# autoset-sensing.net
KiCad netlist of a schematic drawn in EAGLE
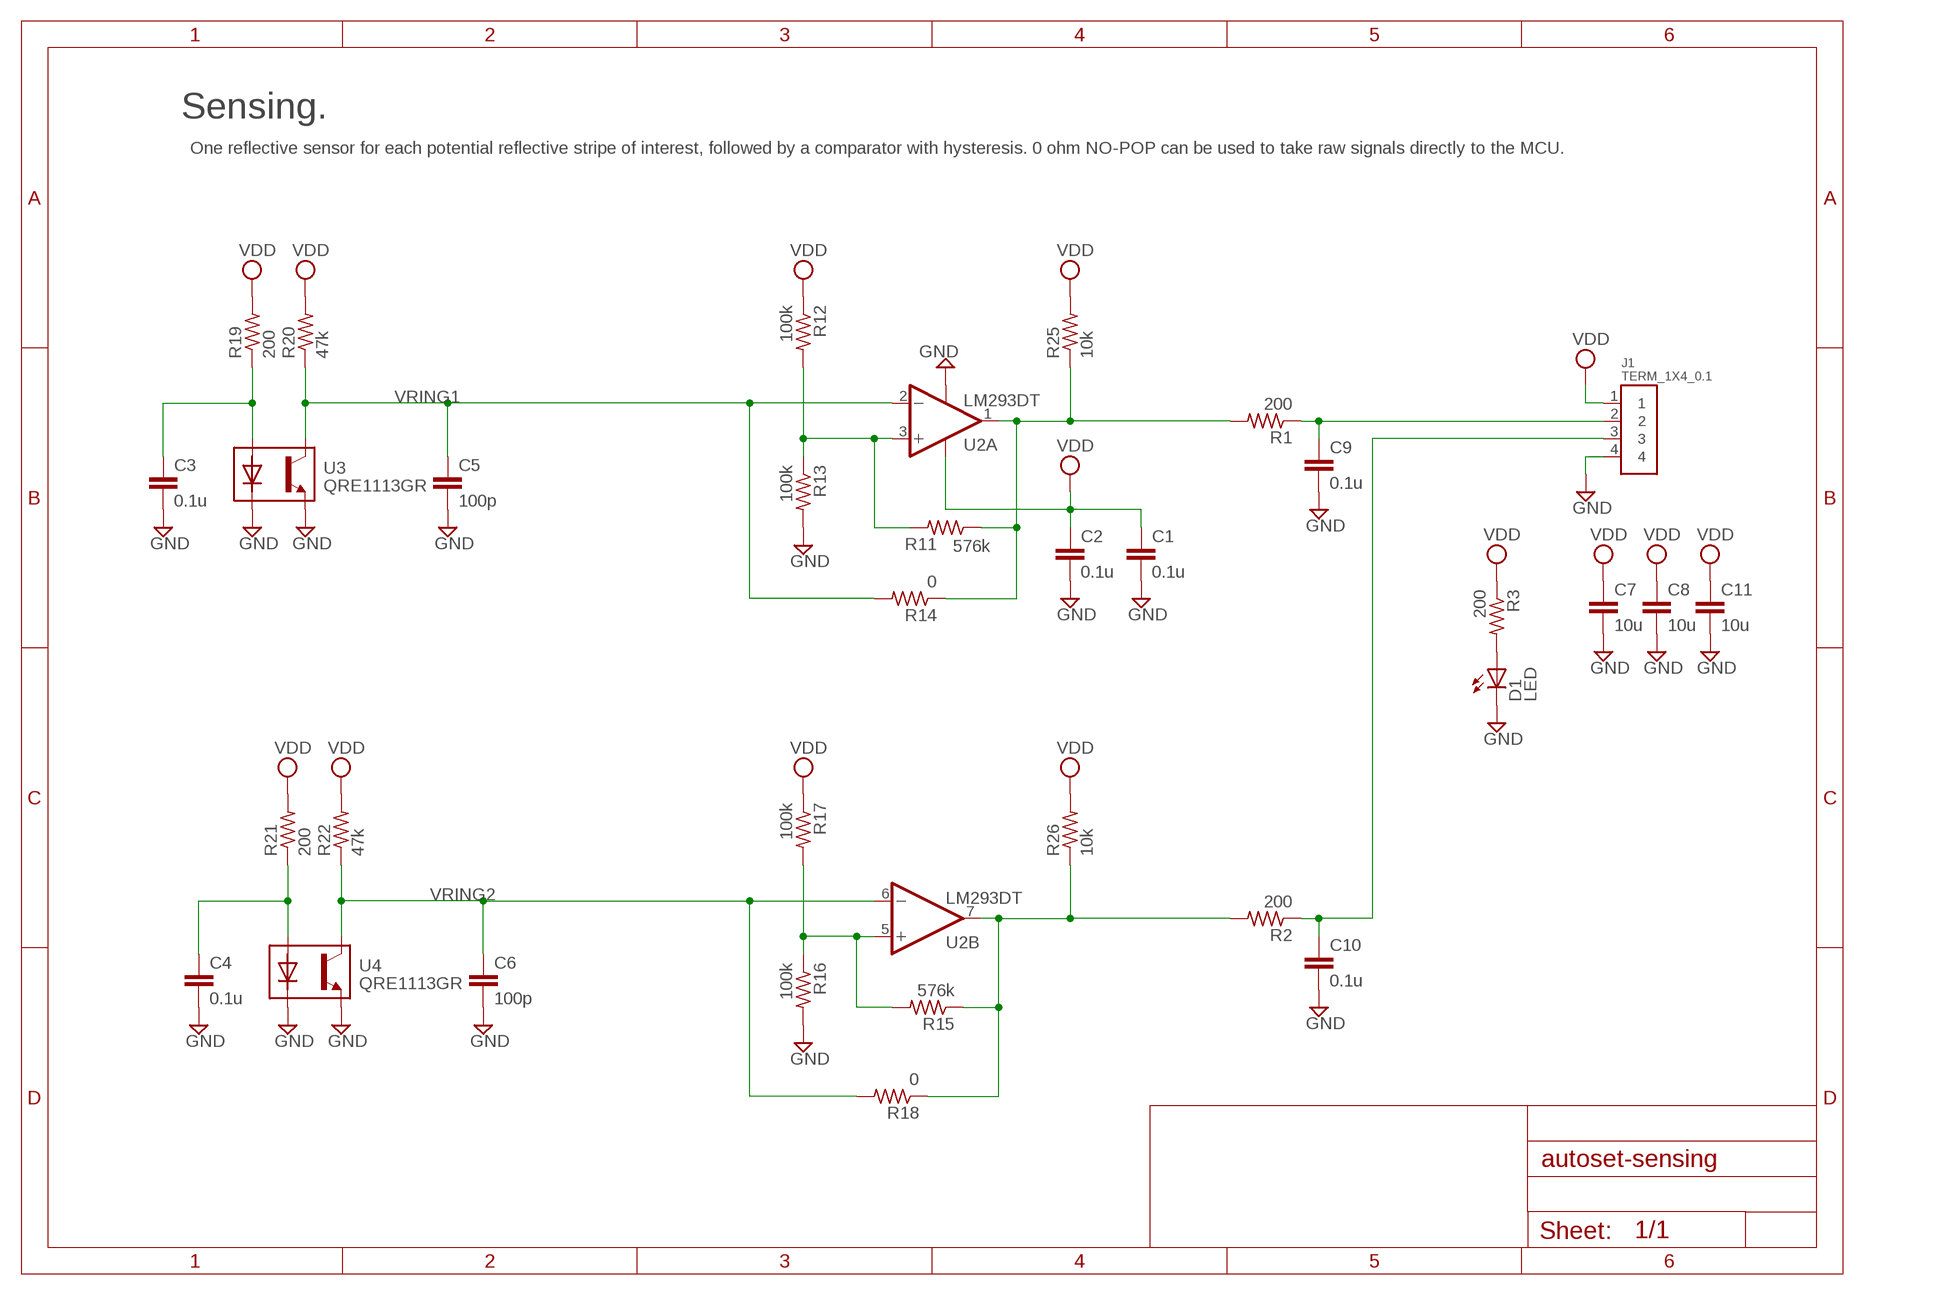
[diagram p0: schematic, sheet 1]

(export (version "E")
  (design (tool "Eeschema 10.0.6"))
  (components
    (comp (ref "C1")
      (value "0.1u")
      (footprint "eagle-import:C0603")
      (libsource (lib "eagle-import") (part "C0603"))
    )
    (comp (ref "C2")
      (value "0.1u")
      (footprint "eagle-import:C0603")
      (libsource (lib "eagle-import") (part "C0603"))
    )
    (comp (ref "C3")
      (value "0.1u")
      (footprint "eagle-import:C0603")
      (libsource (lib "eagle-import") (part "C0603"))
    )
    (comp (ref "C4")
      (value "0.1u")
      (footprint "eagle-import:C0603")
      (libsource (lib "eagle-import") (part "C0603"))
    )
    (comp (ref "C5")
      (value "100p")
      (footprint "eagle-import:C0603")
      (libsource (lib "eagle-import") (part "C0603"))
    )
    (comp (ref "C6")
      (value "100p")
      (footprint "eagle-import:C0603")
      (libsource (lib "eagle-import") (part "C0603"))
    )
    (comp (ref "C7")
      (value "10u")
      (footprint "eagle-import:C0603")
      (libsource (lib "eagle-import") (part "C0603"))
    )
    (comp (ref "C8")
      (value "10u")
      (footprint "eagle-import:C0603")
      (libsource (lib "eagle-import") (part "C0603"))
    )
    (comp (ref "C9")
      (value "0.1u")
      (footprint "eagle-import:C0603")
      (libsource (lib "eagle-import") (part "C0603"))
    )
    (comp (ref "C10")
      (value "0.1u")
      (footprint "eagle-import:C0603")
      (libsource (lib "eagle-import") (part "C0603"))
    )
    (comp (ref "C11")
      (value "10u")
      (footprint "eagle-import:C0603")
      (libsource (lib "eagle-import") (part "C0603"))
    )
    (comp (ref "D1")
      (value "LED")
      (footprint "eagle-import:L0805")
      (libsource (lib "eagle-import") (part "LED"))
    )
    (comp (ref "J1")
      (value "TERM_1X4_0.1")
      (footprint "eagle-import:TERM_1X4_0.1")
      (libsource (lib "eagle-import") (part "TERM_1X4_0.1"))
    )
    (comp (ref "R1")
      (value "200")
      (footprint "eagle-import:R0603")
      (libsource (lib "eagle-import") (part "R0603"))
    )
    (comp (ref "R2")
      (value "200")
      (footprint "eagle-import:R0603")
      (libsource (lib "eagle-import") (part "R0603"))
    )
    (comp (ref "R3")
      (value "200")
      (footprint "eagle-import:R0603")
      (libsource (lib "eagle-import") (part "R0603"))
    )
    (comp (ref "R11")
      (value "576k")
      (footprint "eagle-import:R0603")
      (libsource (lib "eagle-import") (part "R0603"))
    )
    (comp (ref "R12")
      (value "100k")
      (footprint "eagle-import:R0603")
      (libsource (lib "eagle-import") (part "R0603"))
    )
    (comp (ref "R13")
      (value "100k")
      (footprint "eagle-import:R0603")
      (libsource (lib "eagle-import") (part "R0603"))
    )
    (comp (ref "R14")
      (value "0")
      (footprint "eagle-import:R0603")
      (libsource (lib "eagle-import") (part "R0603"))
    )
    (comp (ref "R15")
      (value "576k")
      (footprint "eagle-import:R0603")
      (libsource (lib "eagle-import") (part "R0603"))
    )
    (comp (ref "R16")
      (value "100k")
      (footprint "eagle-import:R0603")
      (libsource (lib "eagle-import") (part "R0603"))
    )
    (comp (ref "R17")
      (value "100k")
      (footprint "eagle-import:R0603")
      (libsource (lib "eagle-import") (part "R0603"))
    )
    (comp (ref "R18")
      (value "0")
      (footprint "eagle-import:R0603")
      (libsource (lib "eagle-import") (part "R0603"))
    )
    (comp (ref "R19")
      (value "200")
      (footprint "eagle-import:R0603")
      (libsource (lib "eagle-import") (part "R0603"))
    )
    (comp (ref "R20")
      (value "47k")
      (footprint "eagle-import:R0603")
      (libsource (lib "eagle-import") (part "R0603"))
    )
    (comp (ref "R21")
      (value "200")
      (footprint "eagle-import:R0603")
      (libsource (lib "eagle-import") (part "R0603"))
    )
    (comp (ref "R22")
      (value "47k")
      (footprint "eagle-import:R0603")
      (libsource (lib "eagle-import") (part "R0603"))
    )
    (comp (ref "R25")
      (value "10k")
      (footprint "eagle-import:R0603")
      (libsource (lib "eagle-import") (part "R0603"))
    )
    (comp (ref "R26")
      (value "10k")
      (footprint "eagle-import:R0603")
      (libsource (lib "eagle-import") (part "R0603"))
    )
    (comp (ref "U2")
      (value "LM293DT")
      (footprint "eagle-import:SOIC8")
      (fields (field (name "DKPN") "497-1566-1-ND"))
      (libsource (lib "eagle-import") (part "LM293DT"))
    )
    (comp (ref "U3")
      (value "QRE1113GR")
      (footprint "eagle-import:REFL")
      (libsource (lib "eagle-import") (part "QRE1113GR"))
    )
    (comp (ref "U4")
      (value "QRE1113GR")
      (footprint "eagle-import:REFL")
      (libsource (lib "eagle-import") (part "QRE1113GR"))
    )
  )
  (nets
    (net (code "1") (name "/VRING1") (class "Default")
      (node (ref "C5") (pin "1") (pinfunction "1_1") (pintype "passive"))
      (node (ref "R14") (pin "2") (pinfunction "2_2") (pintype "passive"))
      (node (ref "R20") (pin "1") (pinfunction "1_1") (pintype "passive"))
      (node (ref "U2") (pin "2") (pinfunction "-IN_2") (pintype "input"))
      (node (ref "U3") (pin "3") (pinfunction "C_3") (pintype "passive"))
    )
    (net (code "2") (name "/VRING2") (class "Default")
      (node (ref "C6") (pin "1") (pinfunction "1_1") (pintype "passive"))
      (node (ref "R18") (pin "2") (pinfunction "2_2") (pintype "passive"))
      (node (ref "R22") (pin "1") (pinfunction "1_1") (pintype "passive"))
      (node (ref "U2") (pin "6") (pinfunction "-IN_6") (pintype "input"))
      (node (ref "U4") (pin "3") (pinfunction "C_3") (pintype "passive"))
    )
    (net (code "3") (name "GND") (class "Default")
      (node (ref "C1") (pin "2") (pinfunction "2_2") (pintype "passive"))
      (node (ref "C10") (pin "2") (pinfunction "2_2") (pintype "passive"))
      (node (ref "C11") (pin "2") (pinfunction "2_2") (pintype "passive"))
      (node (ref "C2") (pin "2") (pinfunction "2_2") (pintype "passive"))
      (node (ref "C3") (pin "2") (pinfunction "2_2") (pintype "passive"))
      (node (ref "C4") (pin "2") (pinfunction "2_2") (pintype "passive"))
      (node (ref "C5") (pin "2") (pinfunction "2_2") (pintype "passive"))
      (node (ref "C6") (pin "2") (pinfunction "2_2") (pintype "passive"))
      (node (ref "C7") (pin "2") (pinfunction "2_2") (pintype "passive"))
      (node (ref "C8") (pin "2") (pinfunction "2_2") (pintype "passive"))
      (node (ref "C9") (pin "2") (pinfunction "2_2") (pintype "passive"))
      (node (ref "D1") (pin "2") (pinfunction "C_2") (pintype "passive"))
      (node (ref "J1") (pin "4") (pinfunction "4_4") (pintype "bidirectional"))
      (node (ref "R13") (pin "2") (pinfunction "2_2") (pintype "passive"))
      (node (ref "R16") (pin "2") (pinfunction "2_2") (pintype "passive"))
      (node (ref "U2") (pin "4") (pinfunction "V-_4") (pintype "power_in"))
      (node (ref "U3") (pin "2") (pinfunction "DC_2") (pintype "passive"))
      (node (ref "U3") (pin "4") (pinfunction "E_4") (pintype "passive"))
      (node (ref "U4") (pin "2") (pinfunction "DC_2") (pintype "passive"))
      (node (ref "U4") (pin "4") (pinfunction "E_4") (pintype "passive"))
    )
    (net (code "4") (name "Net-(C9-Pad1)") (class "Default")
      (node (ref "C9") (pin "1") (pinfunction "1_1") (pintype "passive"))
      (node (ref "J1") (pin "2") (pinfunction "2_2") (pintype "bidirectional"))
      (node (ref "R1") (pin "1") (pinfunction "1_1") (pintype "passive"))
    )
    (net (code "5") (name "Net-(C10-Pad1)") (class "Default")
      (node (ref "C10") (pin "1") (pinfunction "1_1") (pintype "passive"))
      (node (ref "J1") (pin "3") (pinfunction "3_3") (pintype "bidirectional"))
      (node (ref "R2") (pin "1") (pinfunction "1_1") (pintype "passive"))
    )
    (net (code "6") (name "Net-(D1-A)") (class "Default")
      (node (ref "D1") (pin "1") (pinfunction "A_1") (pintype "passive"))
      (node (ref "R3") (pin "2") (pinfunction "2_2") (pintype "passive"))
    )
    (net (code "7") (name "Net-(U2A-+IN)") (class "Default")
      (node (ref "R11") (pin "2") (pinfunction "2_2") (pintype "passive"))
      (node (ref "R12") (pin "2") (pinfunction "2_2") (pintype "passive"))
      (node (ref "R13") (pin "1") (pinfunction "1_1") (pintype "passive"))
      (node (ref "U2") (pin "3") (pinfunction "+IN_3") (pintype "input"))
    )
    (net (code "8") (name "Net-(U2A-OUT)") (class "Default")
      (node (ref "R1") (pin "2") (pinfunction "2_2") (pintype "passive"))
      (node (ref "R11") (pin "1") (pinfunction "1_1") (pintype "passive"))
      (node (ref "R14") (pin "1") (pinfunction "1_1") (pintype "passive"))
      (node (ref "R25") (pin "1") (pinfunction "1_1") (pintype "passive"))
      (node (ref "U2") (pin "1") (pinfunction "OUT_1") (pintype "output"))
    )
    (net (code "9") (name "Net-(U2B-+IN)") (class "Default")
      (node (ref "R15") (pin "2") (pinfunction "2_2") (pintype "passive"))
      (node (ref "R16") (pin "1") (pinfunction "1_1") (pintype "passive"))
      (node (ref "R17") (pin "2") (pinfunction "2_2") (pintype "passive"))
      (node (ref "U2") (pin "5") (pinfunction "+IN_5") (pintype "input"))
    )
    (net (code "10") (name "Net-(U2B-OUT)") (class "Default")
      (node (ref "R15") (pin "1") (pinfunction "1_1") (pintype "passive"))
      (node (ref "R18") (pin "1") (pinfunction "1_1") (pintype "passive"))
      (node (ref "R2") (pin "2") (pinfunction "2_2") (pintype "passive"))
      (node (ref "R26") (pin "1") (pinfunction "1_1") (pintype "passive"))
      (node (ref "U2") (pin "7") (pinfunction "OUT_7") (pintype "output"))
    )
    (net (code "11") (name "Net-(U3-DA)") (class "Default")
      (node (ref "C3") (pin "1") (pinfunction "1_1") (pintype "passive"))
      (node (ref "R19") (pin "1") (pinfunction "1_1") (pintype "passive"))
      (node (ref "U3") (pin "1") (pinfunction "DA_1") (pintype "passive"))
    )
    (net (code "12") (name "Net-(U4-DA)") (class "Default")
      (node (ref "C4") (pin "1") (pinfunction "1_1") (pintype "passive"))
      (node (ref "R21") (pin "1") (pinfunction "1_1") (pintype "passive"))
      (node (ref "U4") (pin "1") (pinfunction "DA_1") (pintype "passive"))
    )
    (net (code "13") (name "VDD") (class "Default")
      (node (ref "C1") (pin "1") (pinfunction "1_1") (pintype "passive"))
      (node (ref "C11") (pin "1") (pinfunction "1_1") (pintype "passive"))
      (node (ref "C2") (pin "1") (pinfunction "1_1") (pintype "passive"))
      (node (ref "C7") (pin "1") (pinfunction "1_1") (pintype "passive"))
      (node (ref "C8") (pin "1") (pinfunction "1_1") (pintype "passive"))
      (node (ref "J1") (pin "1") (pinfunction "1_1") (pintype "bidirectional"))
      (node (ref "R12") (pin "1") (pinfunction "1_1") (pintype "passive"))
      (node (ref "R17") (pin "1") (pinfunction "1_1") (pintype "passive"))
      (node (ref "R19") (pin "2") (pinfunction "2_2") (pintype "passive"))
      (node (ref "R20") (pin "2") (pinfunction "2_2") (pintype "passive"))
      (node (ref "R21") (pin "2") (pinfunction "2_2") (pintype "passive"))
      (node (ref "R22") (pin "2") (pinfunction "2_2") (pintype "passive"))
      (node (ref "R25") (pin "2") (pinfunction "2_2") (pintype "passive"))
      (node (ref "R26") (pin "2") (pinfunction "2_2") (pintype "passive"))
      (node (ref "R3") (pin "1") (pinfunction "1_1") (pintype "passive"))
      (node (ref "U2") (pin "8") (pinfunction "V+_8") (pintype "power_in"))
    )
  )
)
